# Power_Stage.net
KiCad netlist of a schematic drawn in Altium Designer
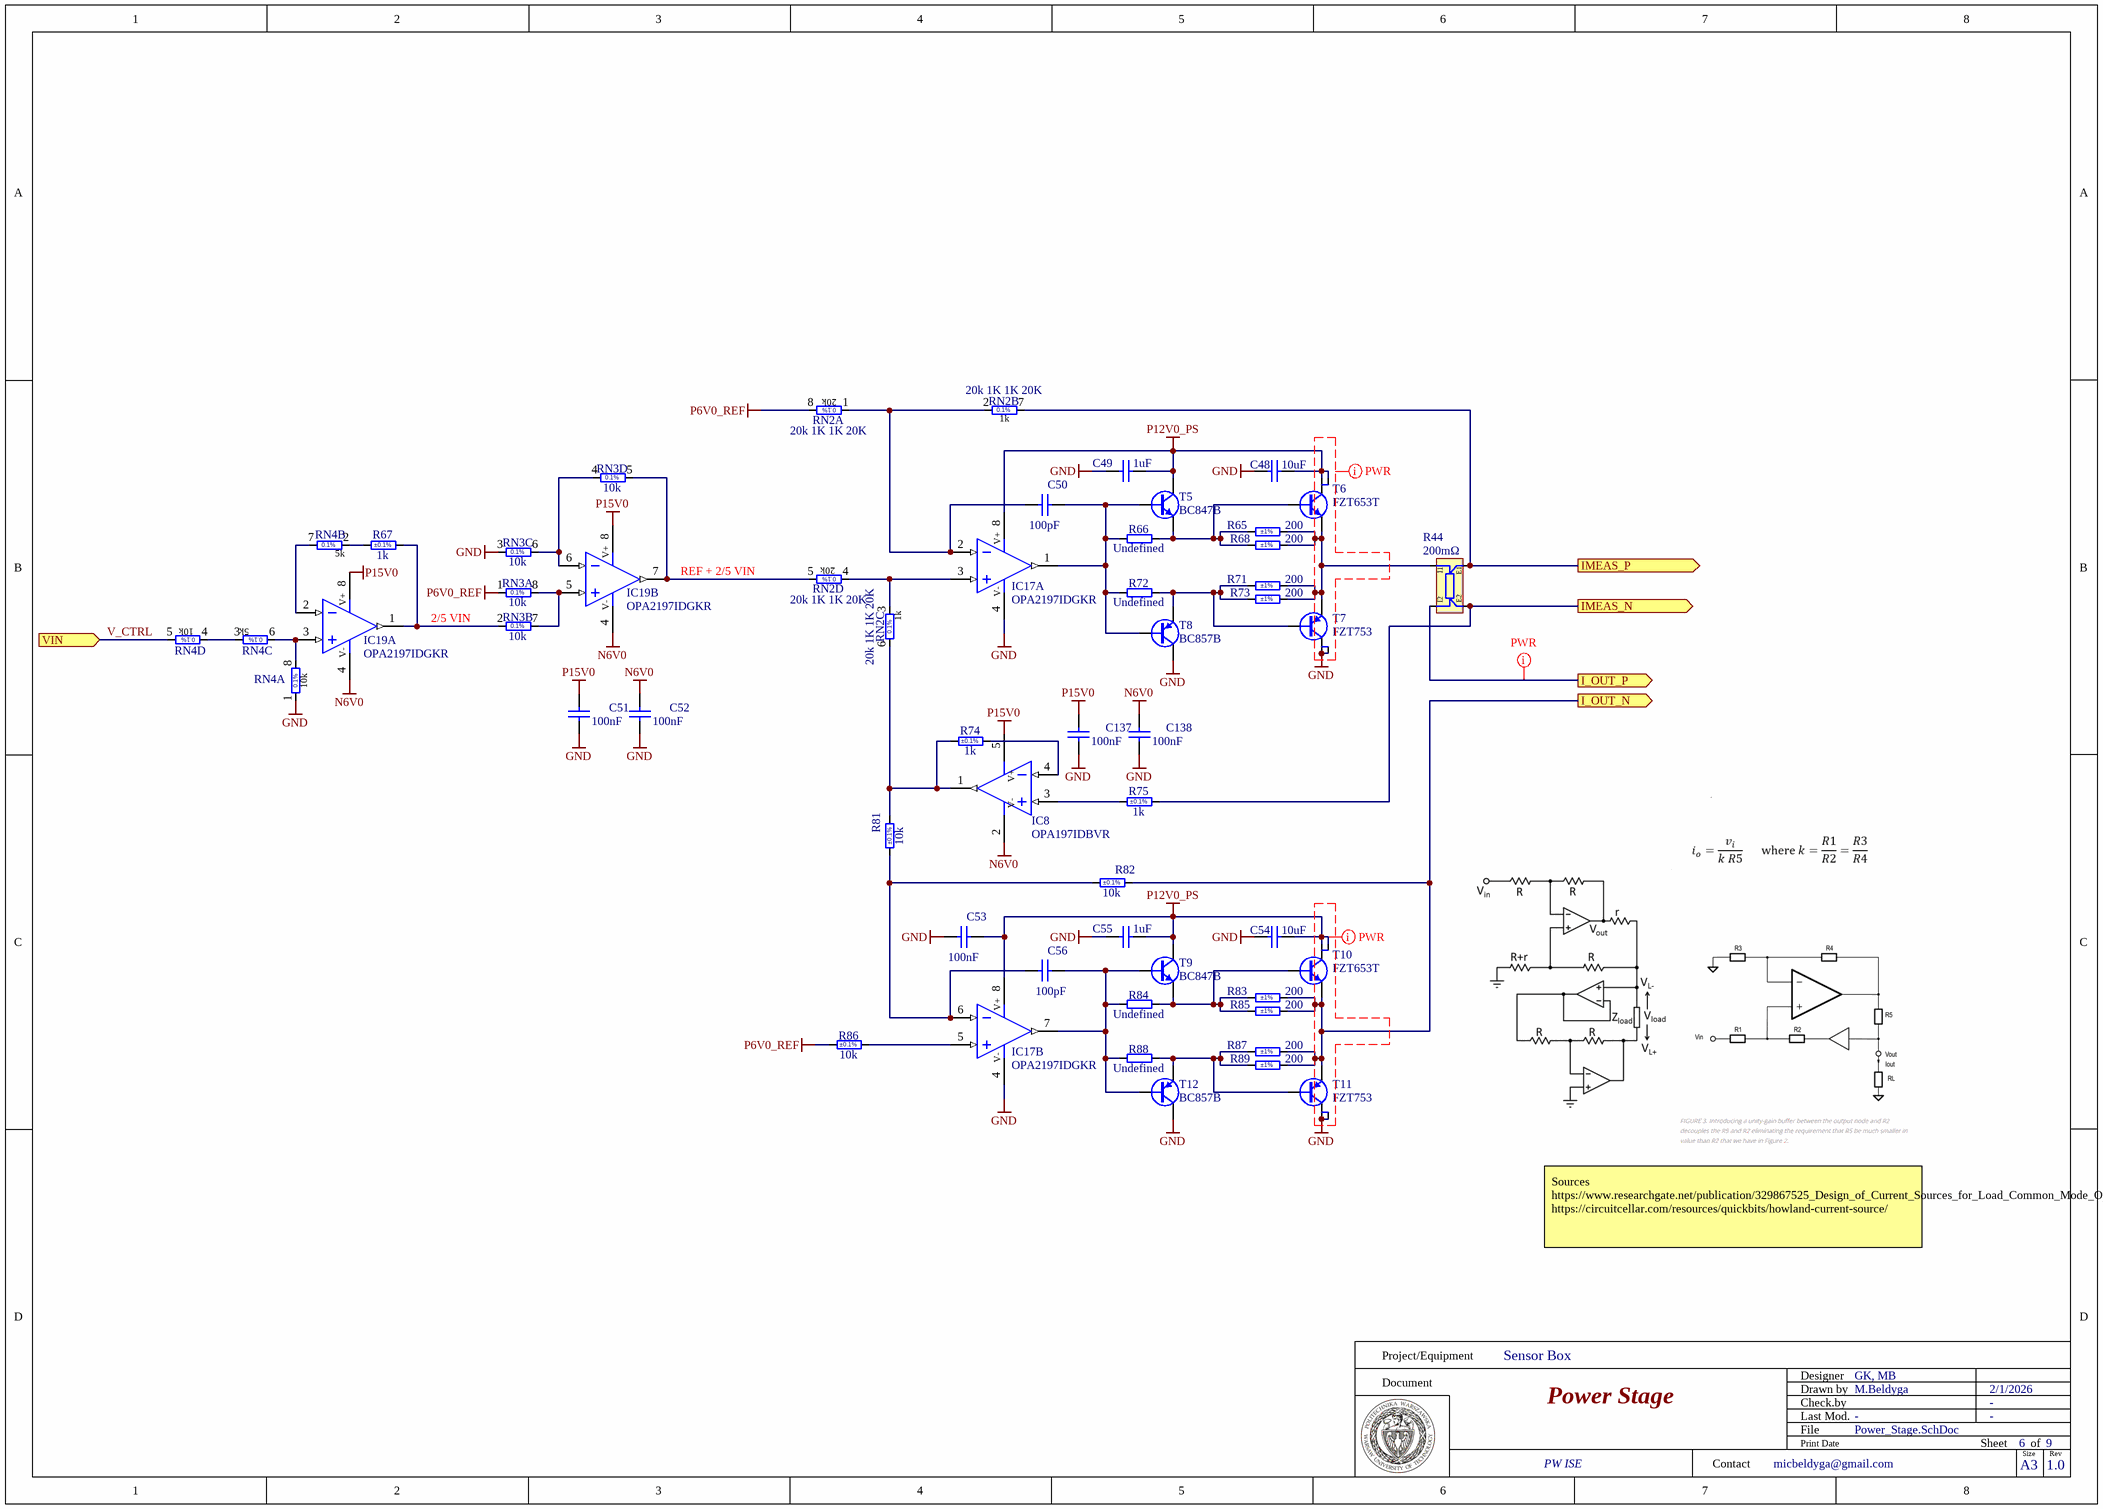
[diagram p0: Power_Stage.SchDoc]

(export (version "E")
  (design (tool "Eeschema 10.0.6"))
  (components
    (comp (ref "C48")
      (value "10uF")
      (footprint "CAPC2012X95N")
      (description "Non-polarised capacitor")
      (fields
        (field (name "PART NUMBER") "CC0805_10UF_25V_10%_X5R")
        (field (name "VOLTAGE") "25V")
        (field (name "AUTHOR") "CERN DEM JLC")
      )
      (libsource (lib "Capacitors") (part "Capacitor - non polarized"))
    )
    (comp (ref "C49")
      (value "1uF")
      (footprint "CAPC1608X87N")
      (description "Non-polarised capacitor")
      (fields
        (field (name "PART NUMBER") "CC0603_1UF_25V_10%_X7R")
        (field (name "VOLTAGE") "25V")
        (field (name "AUTHOR") "CERN DEM JLC")
      )
      (libsource (lib "Capacitors") (part "Capacitor - non polarized"))
    )
    (comp (ref "C50")
      (value "100pF")
      (footprint "CAPC1005X55N")
      (description "Non-polarised capacitor")
      (fields
        (field (name "PART NUMBER") "CC0402_100PF_50V_5%_C0G")
        (field (name "VOLTAGE") "50V")
        (field (name "AUTHOR") "CERN DEM JLC")
      )
      (libsource (lib "Capacitors") (part "Capacitor - non polarized"))
    )
    (comp (ref "C51")
      (value "100nF")
      (footprint "CAPC1005X55N")
      (description "Non-polarised capacitor")
      (fields
        (field (name "PART NUMBER") "CC0402_100NF_16V_10%_X5R")
        (field (name "VOLTAGE") "16V")
        (field (name "AUTHOR") "CERN DEM JLC")
      )
      (libsource (lib "Capacitors") (part "Capacitor - non polarized"))
    )
    (comp (ref "C52")
      (value "100nF")
      (footprint "CAPC1005X55N")
      (description "Non-polarised capacitor")
      (fields
        (field (name "PART NUMBER") "CC0402_100NF_16V_10%_X5R")
        (field (name "VOLTAGE") "16V")
        (field (name "AUTHOR") "CERN DEM JLC")
      )
      (libsource (lib "Capacitors") (part "Capacitor - non polarized"))
    )
    (comp (ref "C53")
      (value "100nF")
      (footprint "CAPC1005X55N")
      (description "Non-polarised capacitor")
      (fields
        (field (name "PART NUMBER") "CC0402_100NF_16V_10%_X5R")
        (field (name "VOLTAGE") "16V")
        (field (name "AUTHOR") "CERN DEM JLC")
      )
      (libsource (lib "Capacitors") (part "Capacitor - non polarized"))
    )
    (comp (ref "C54")
      (value "10uF")
      (footprint "CAPC2012X95N")
      (description "Non-polarised capacitor")
      (fields
        (field (name "PART NUMBER") "CC0805_10UF_25V_10%_X5R")
        (field (name "VOLTAGE") "25V")
        (field (name "AUTHOR") "CERN DEM JLC")
      )
      (libsource (lib "Capacitors") (part "Capacitor - non polarized"))
    )
    (comp (ref "C55")
      (value "1uF")
      (footprint "CAPC1608X87N")
      (description "Non-polarised capacitor")
      (fields
        (field (name "PART NUMBER") "CC0603_1UF_25V_10%_X7R")
        (field (name "VOLTAGE") "25V")
        (field (name "AUTHOR") "CERN DEM JLC")
      )
      (libsource (lib "Capacitors") (part "Capacitor - non polarized"))
    )
    (comp (ref "C56")
      (value "100pF")
      (footprint "CAPC1005X55N")
      (description "Non-polarised capacitor")
      (fields
        (field (name "PART NUMBER") "CC0402_100PF_50V_5%_C0G")
        (field (name "VOLTAGE") "50V")
        (field (name "AUTHOR") "CERN DEM JLC")
      )
      (libsource (lib "Capacitors") (part "Capacitor - non polarized"))
    )
    (comp (ref "C137")
      (value "100nF")
      (footprint "CAPC1005X55N")
      (description "Non-polarised capacitor")
      (fields
        (field (name "PART NUMBER") "CC0402_100NF_16V_10%_X5R")
        (field (name "VOLTAGE") "16V")
        (field (name "AUTHOR") "CERN DEM JLC")
      )
      (libsource (lib "Capacitors") (part "Capacitor - non polarized"))
    )
    (comp (ref "C138")
      (value "100nF")
      (footprint "CAPC1005X55N")
      (description "Non-polarised capacitor")
      (fields
        (field (name "PART NUMBER") "CC0402_100NF_16V_10%_X5R")
        (field (name "VOLTAGE") "16V")
        (field (name "AUTHOR") "CERN DEM JLC")
      )
      (libsource (lib "Capacitors") (part "Capacitor - non polarized"))
    )
    (comp (ref "IC8")
      (value "OPA197IDBVR")
      (footprint "SOT95P280X145-5N")
      (description "Op Amp Single Precision Amplifier R-R I/O ±18V/36V 5-Pin SOT-23 T/R")
      (fields (field (name "MANUFACTURER") "Texas Instruments"))
      (libsource (lib "mb") (part "OPA197IDBVR"))
    )
    (comp (ref "IC17")
      (value "OPA2197IDGKR")
      (footprint "SOP65P490X110-8N")
      (description "36-V, Precision, Rail-to-Rail Input Output, Low Offset Voltage Op Amp 8-VSSOP")
      (fields (field (name "AUTHOR") "GK"))
      (libsource (lib "ICs_Analog_Interfaces") (part "OA_OPA2197IDGKR"))
    )
    (comp (ref "IC19")
      (value "OPA2197IDGKR")
      (footprint "SOP65P490X110-8N")
      (description "36-V, Precision, Rail-to-Rail Input Output, Low Offset Voltage Op Amp 8-VSSOP")
      (fields (field (name "AUTHOR") "GK"))
      (libsource (lib "ICs_Analog_Interfaces") (part "OA_OPA2197IDGKR"))
    )
    (comp (ref "R44")
      (value "200mΩ")
      (footprint "RES_VISHAY_CSM2512_0R007-0R2")
      (description "Fixed Resistor, Metal Strip, 1W, 0.2ohm, 0.447V, 0.1% +/-Tol, 15ppm/Cel, Surface Mount, 2512")
      (fields
        (field (name "MANUFACTURER") "VPG Foil Resistors")
        (field (name "MANUFACTURER PART NUMBER") "Y14870R20000B9R")
      )
      (libsource (lib "mb") (part "Y14870R20000B9R"))
    )
    (comp (ref "R65")
      (value "200")
      (footprint "RESC1608X55N")
      (description "Resistor - 1%")
      (fields
        (field (name "TOLERANCE") "±1%")
        (field (name "PART NUMBER") "R0603_200R_1%_0.1W_100PPM")
        (field (name "POWER") "0.1W")
        (field (name "AUTHOR") "CERN DEM JLC")
      )
      (libsource (lib "Resistors") (part "Resistor - 1%"))
    )
    (comp (ref "R66")
      (value "Undefined")
      (footprint "RESC1608X55N")
      (description "Resistor")
      (fields (field (name "PART NUMBER") "R0603_NO-VALUE") (field (name "AUTHOR") "CERN DEM JLC"))
      (libsource (lib "Resistors") (part "Resistor"))
    )
    (comp (ref "R67")
      (value "1k")
      (footprint "RESC1005X40N")
      (description "Resistor - 0.1%")
      (fields
        (field (name "TOLERANCE") "±0.1%")
        (field (name "PART NUMBER") "R0402_1K_0.1%_0.063W_25PPM")
        (field (name "POWER") "0.063W")
        (field (name "AUTHOR") "CERN DEM BC")
      )
      (libsource (lib "Resistors") (part "Resistor - 0.1%"))
    )
    (comp (ref "R68")
      (value "200")
      (footprint "RESC1608X55N")
      (description "Resistor - 1%")
      (fields
        (field (name "TOLERANCE") "±1%")
        (field (name "PART NUMBER") "R0603_200R_1%_0.1W_100PPM")
        (field (name "POWER") "0.1W")
        (field (name "AUTHOR") "CERN DEM JLC")
      )
      (libsource (lib "Resistors") (part "Resistor - 1%"))
    )
    (comp (ref "R71")
      (value "200")
      (footprint "RESC1608X55N")
      (description "Resistor - 1%")
      (fields
        (field (name "TOLERANCE") "±1%")
        (field (name "PART NUMBER") "R0603_200R_1%_0.1W_100PPM")
        (field (name "POWER") "0.1W")
        (field (name "AUTHOR") "CERN DEM JLC")
      )
      (libsource (lib "Resistors") (part "Resistor - 1%"))
    )
    (comp (ref "R72")
      (value "Undefined")
      (footprint "RESC1608X55N")
      (description "Resistor")
      (fields (field (name "PART NUMBER") "R0603_NO-VALUE") (field (name "AUTHOR") "CERN DEM JLC"))
      (libsource (lib "Resistors") (part "Resistor"))
    )
    (comp (ref "R73")
      (value "200")
      (footprint "RESC1608X55N")
      (description "Resistor - 1%")
      (fields
        (field (name "TOLERANCE") "±1%")
        (field (name "PART NUMBER") "R0603_200R_1%_0.1W_100PPM")
        (field (name "POWER") "0.1W")
        (field (name "AUTHOR") "CERN DEM JLC")
      )
      (libsource (lib "Resistors") (part "Resistor - 1%"))
    )
    (comp (ref "R74")
      (value "1k")
      (footprint "RESC1005X40N")
      (description "Resistor - 0.1%")
      (fields
        (field (name "TOLERANCE") "±0.1%")
        (field (name "PART NUMBER") "R0402_1K_0.1%_0.063W_25PPM")
        (field (name "POWER") "0.063W")
        (field (name "AUTHOR") "CERN DEM BC")
      )
      (libsource (lib "Resistors") (part "Resistor - 0.1%"))
    )
    (comp (ref "R75")
      (value "1k")
      (footprint "RESC1005X40N")
      (description "Resistor - 0.1%")
      (fields
        (field (name "TOLERANCE") "±0.1%")
        (field (name "PART NUMBER") "R0402_1K_0.1%_0.063W_25PPM")
        (field (name "POWER") "0.063W")
        (field (name "AUTHOR") "CERN DEM BC")
      )
      (libsource (lib "Resistors") (part "Resistor - 0.1%"))
    )
    (comp (ref "R81")
      (value "10k")
      (footprint "RESC1005X35N")
      (description "Resistor - 0.1%")
      (fields
        (field (name "TOLERANCE") "±0.1%")
        (field (name "PART NUMBER") "R0402_10K_0.1%_0.063W_25PPM")
        (field (name "POWER") "0.063W")
        (field (name "AUTHOR") "CERN DEM JMW")
      )
      (libsource (lib "Resistors") (part "Resistor - 0.1%"))
    )
    (comp (ref "R82")
      (value "10k")
      (footprint "RESC1005X35N")
      (description "Resistor - 0.1%")
      (fields
        (field (name "TOLERANCE") "±0.1%")
        (field (name "PART NUMBER") "R0402_10K_0.1%_0.063W_25PPM")
        (field (name "POWER") "0.063W")
        (field (name "AUTHOR") "CERN DEM JMW")
      )
      (libsource (lib "Resistors") (part "Resistor - 0.1%"))
    )
    (comp (ref "R83")
      (value "200")
      (footprint "RESC1608X55N")
      (description "Resistor - 1%")
      (fields
        (field (name "TOLERANCE") "±1%")
        (field (name "PART NUMBER") "R0603_200R_1%_0.1W_100PPM")
        (field (name "POWER") "0.1W")
        (field (name "AUTHOR") "CERN DEM JLC")
      )
      (libsource (lib "Resistors") (part "Resistor - 1%"))
    )
    (comp (ref "R84")
      (value "Undefined")
      (footprint "RESC1608X55N")
      (description "Resistor")
      (fields (field (name "PART NUMBER") "R0603_NO-VALUE") (field (name "AUTHOR") "CERN DEM JLC"))
      (libsource (lib "Resistors") (part "Resistor"))
    )
    (comp (ref "R85")
      (value "200")
      (footprint "RESC1608X55N")
      (description "Resistor - 1%")
      (fields
        (field (name "TOLERANCE") "±1%")
        (field (name "PART NUMBER") "R0603_200R_1%_0.1W_100PPM")
        (field (name "POWER") "0.1W")
        (field (name "AUTHOR") "CERN DEM JLC")
      )
      (libsource (lib "Resistors") (part "Resistor - 1%"))
    )
    (comp (ref "R86")
      (value "10k")
      (footprint "RESC1005X35N")
      (description "Resistor - 0.1%")
      (fields
        (field (name "TOLERANCE") "±0.1%")
        (field (name "PART NUMBER") "R0402_10K_0.1%_0.063W_25PPM")
        (field (name "POWER") "0.063W")
        (field (name "AUTHOR") "CERN DEM JMW")
      )
      (libsource (lib "Resistors") (part "Resistor - 0.1%"))
    )
    (comp (ref "R87")
      (value "200")
      (footprint "RESC1608X55N")
      (description "Resistor - 1%")
      (fields
        (field (name "TOLERANCE") "±1%")
        (field (name "PART NUMBER") "R0603_200R_1%_0.1W_100PPM")
        (field (name "POWER") "0.1W")
        (field (name "AUTHOR") "CERN DEM JLC")
      )
      (libsource (lib "Resistors") (part "Resistor - 1%"))
    )
    (comp (ref "R88")
      (value "Undefined")
      (footprint "RESC1608X55N")
      (description "Resistor")
      (fields (field (name "PART NUMBER") "R0603_NO-VALUE") (field (name "AUTHOR") "CERN DEM JLC"))
      (libsource (lib "Resistors") (part "Resistor"))
    )
    (comp (ref "R89")
      (value "200")
      (footprint "RESC1608X55N")
      (description "Resistor - 1%")
      (fields
        (field (name "TOLERANCE") "±1%")
        (field (name "PART NUMBER") "R0603_200R_1%_0.1W_100PPM")
        (field (name "POWER") "0.1W")
        (field (name "AUTHOR") "CERN DEM JLC")
      )
      (libsource (lib "Resistors") (part "Resistor - 1%"))
    )
    (comp (ref "RN2")
      (value "20k 1K 1K 20K")
      (footprint "SOIC127P600X175-8N")
      (description "DIL8 Resistor Network 4 Resistors 4xR 10k-1k-1k-10k 0.1%")
      (fields
        (field (name "PART NUMBER") "RN_20K_1K_VISHAY_AORN10-1A")
        (field (name "POWER") "4x0.1W")
        (field (name "AUTHOR") "GK")
      )
      (libsource (lib "Passives_RC") (part "RN_20K_1K_VISHAY_AORN20-1A"))
    )
    (comp (ref "RN3")
      (value "10k")
      (footprint "SOIC127P600X175-8N")
      (description "DIL8 Resistor Network 4 Isolated Resistor 0.1%")
      (fields
        (field (name "PART NUMBER") "RN_10K_VISHAY_AORN1002A")
        (field (name "POWER") "4x0.1W")
        (field (name "AUTHOR") "CERN DEM JLC")
      )
      (libsource (lib "Resistors") (part "RN DIL8_4xR_Isolated_0.1%"))
    )
    (comp (ref "RN4")
      (value "10k 5K 5K 10K")
      (footprint "SOIC127P600X175-8N")
      (description "DIL8 Resistor Network 4 Resistors 10k-5k-5k-10k 0.1%")
      (fields
        (field (name "PART NUMBER") "RN_10K_5K_VISHAY_AORN2-1AT3")
        (field (name "POWER") "4x0.1W")
        (field (name "AUTHOR") "CERN DEM JLC")
      )
      (libsource (lib "Resistors") (part "RN DIL8_4xR_10k-5k-5k-10k_0.1%"))
    )
    (comp (ref "T5")
      (value "BC847B")
      (footprint "SOT95P230X110-3N")
      (description "NPN Transistor")
      (fields (field (name "MANUFACTURER") "NXP SEMICONDUCTORS") (field (name "AUTHOR") "CERN DEM JLC"))
      (libsource (lib "ICs And Semiconductors") (part "NPN B1 E2 C3"))
    )
    (comp (ref "T6")
      (value "FZT653T")
      (footprint "SOT230P700X180-4N")
      (description "NPN Transistor")
      (fields (field (name "MANUFACTURER") "ZETEX SEMICONDUCTORS") (field (name "AUTHOR") "CERN DEM HF"))
      (libsource (lib "ICs And Semiconductors") (part "NPN B1 C2 E3 C4"))
    )
    (comp (ref "T7")
      (value "FZT753")
      (footprint "SOT230P700X180-4N")
      (description "PNP Transistor")
      (fields (field (name "MANUFACTURER") "DIODES INCORPORATED") (field (name "AUTHOR") "CERN DEM JLC"))
      (libsource (lib "ICs And Semiconductors") (part "PNP B1 C2 E3 C4"))
    )
    (comp (ref "T8")
      (value "BC857B")
      (footprint "SOT95P230X110-3N")
      (description "PNP Transistor")
      (fields (field (name "MANUFACTURER") "NXP SEMICONDUCTORS") (field (name "AUTHOR") "CERN DEM JLC"))
      (libsource (lib "ICs And Semiconductors") (part "PNP B1 E2 C3"))
    )
    (comp (ref "T9")
      (value "BC847B")
      (footprint "SOT95P230X110-3N")
      (description "NPN Transistor")
      (fields (field (name "MANUFACTURER") "NXP SEMICONDUCTORS") (field (name "AUTHOR") "CERN DEM JLC"))
      (libsource (lib "ICs And Semiconductors") (part "NPN B1 E2 C3"))
    )
    (comp (ref "T10")
      (value "FZT653T")
      (footprint "SOT230P700X180-4N")
      (description "NPN Transistor")
      (fields (field (name "MANUFACTURER") "ZETEX SEMICONDUCTORS") (field (name "AUTHOR") "CERN DEM HF"))
      (libsource (lib "ICs And Semiconductors") (part "NPN B1 C2 E3 C4"))
    )
    (comp (ref "T11")
      (value "FZT753")
      (footprint "SOT230P700X180-4N")
      (description "PNP Transistor")
      (fields (field (name "MANUFACTURER") "DIODES INCORPORATED") (field (name "AUTHOR") "CERN DEM JLC"))
      (libsource (lib "ICs And Semiconductors") (part "PNP B1 C2 E3 C4"))
    )
    (comp (ref "T12")
      (value "BC857B")
      (footprint "SOT95P230X110-3N")
      (description "PNP Transistor")
      (fields (field (name "MANUFACTURER") "NXP SEMICONDUCTORS") (field (name "AUTHOR") "CERN DEM JLC"))
      (libsource (lib "ICs And Semiconductors") (part "PNP B1 E2 C3"))
    )
  )
  (nets
    (net (code "1") (name "/IMEAS_N") (class "Default")
      (node (ref "R44") (pin "E2") (pinfunction "E2_E2") (pintype "passive"))
      (node (ref "R75") (pin "2") (pinfunction "2_2") (pintype "passive"))
    )
    (net (code "2") (name "/IMEAS_P") (class "Default")
      (node (ref "R44") (pin "E1") (pinfunction "E1_E1") (pintype "passive"))
      (node (ref "RN2") (pin "7") (pinfunction "7_7") (pintype "passive"))
    )
    (net (code "3") (name "/I_OUT_N") (class "Default")
      (node (ref "R82") (pin "2") (pinfunction "2_2") (pintype "passive"))
      (node (ref "R83") (pin "2") (pinfunction "2_2") (pintype "passive"))
      (node (ref "R85") (pin "2") (pinfunction "2_2") (pintype "passive"))
      (node (ref "R87") (pin "2") (pinfunction "2_2") (pintype "passive"))
      (node (ref "R89") (pin "2") (pinfunction "2_2") (pintype "passive"))
      (node (ref "T10") (pin "3") (pinfunction "E_3") (pintype "passive"))
      (node (ref "T11") (pin "3") (pinfunction "E_3") (pintype "passive"))
    )
    (net (code "4") (name "/I_OUT_P") (class "Default")
      (node (ref "R44") (pin "I2") (pinfunction "I2_I2") (pintype "passive"))
    )
    (net (code "5") (name "/V_CTRL") (class "Default")
      (node (ref "RN4") (pin "5") (pinfunction "5_5") (pintype "passive"))
    )
    (net (code "6") (name "GND") (class "Default")
      (node (ref "C137") (pin "1") (pinfunction "1_1") (pintype "passive"))
      (node (ref "C138") (pin "1") (pinfunction "1_1") (pintype "passive"))
      (node (ref "C48") (pin "2") (pinfunction "2_2") (pintype "passive"))
      (node (ref "C49") (pin "1") (pinfunction "1_1") (pintype "passive"))
      (node (ref "C51") (pin "1") (pinfunction "1_1") (pintype "passive"))
      (node (ref "C52") (pin "1") (pinfunction "1_1") (pintype "passive"))
      (node (ref "C53") (pin "1") (pinfunction "1_1") (pintype "passive"))
      (node (ref "C54") (pin "2") (pinfunction "2_2") (pintype "passive"))
      (node (ref "C55") (pin "1") (pinfunction "1_1") (pintype "passive"))
      (node (ref "IC17") (pin "4") (pinfunction "V-_4") (pintype "power_in"))
      (node (ref "RN3") (pin "3") (pinfunction "3_3") (pintype "passive"))
      (node (ref "RN4") (pin "1") (pinfunction "1_1") (pintype "passive"))
      (node (ref "T11") (pin "2") (pinfunction "C_2") (pintype "passive"))
      (node (ref "T11") (pin "4") (pinfunction "C_4") (pintype "passive"))
      (node (ref "T12") (pin "3") (pinfunction "C_3") (pintype "passive"))
      (node (ref "T7") (pin "2") (pinfunction "C_2") (pintype "passive"))
      (node (ref "T7") (pin "4") (pinfunction "C_4") (pintype "passive"))
      (node (ref "T8") (pin "3") (pinfunction "C_3") (pintype "passive"))
    )
    (net (code "7") (name "N6V0") (class "Default")
      (node (ref "C138") (pin "2") (pinfunction "2_2") (pintype "passive"))
      (node (ref "C52") (pin "2") (pinfunction "2_2") (pintype "passive"))
      (node (ref "IC19") (pin "4") (pinfunction "V-_4") (pintype "power_in"))
      (node (ref "IC8") (pin "2") (pinfunction "V-_2") (pintype "power_in"))
    )
    (net (code "8") (name "Net-(IC8-IN+)") (class "Default")
      (node (ref "IC8") (pin "3") (pinfunction "IN+_3") (pintype "input"))
      (node (ref "R75") (pin "1") (pinfunction "1_1") (pintype "passive"))
    )
    (net (code "9") (name "Net-(IC8-IN-)") (class "Default")
      (node (ref "IC8") (pin "4") (pinfunction "IN-_4") (pintype "input"))
      (node (ref "R74") (pin "2") (pinfunction "2_2") (pintype "passive"))
    )
    (net (code "10") (name "Net-(IC8-OUT)") (class "Default")
      (node (ref "IC8") (pin "1") (pinfunction "OUT_1") (pintype "output"))
      (node (ref "R74") (pin "1") (pinfunction "1_1") (pintype "passive"))
      (node (ref "R81") (pin "2") (pinfunction "2_2") (pintype "passive"))
      (node (ref "RN2") (pin "6") (pinfunction "6_6") (pintype "passive"))
    )
    (net (code "11") (name "Net-(IC17A-IN+)") (class "Default")
      (node (ref "IC17") (pin "3") (pinfunction "IN+_3") (pintype "input"))
      (node (ref "RN2") (pin "3") (pinfunction "3_3") (pintype "passive"))
      (node (ref "RN2") (pin "4") (pinfunction "4_4") (pintype "passive"))
    )
    (net (code "12") (name "Net-(IC17A-IN-)") (class "Default")
      (node (ref "C50") (pin "1") (pinfunction "1_1") (pintype "passive"))
      (node (ref "IC17") (pin "2") (pinfunction "IN-_2") (pintype "input"))
      (node (ref "RN2") (pin "1") (pinfunction "1_1") (pintype "passive"))
      (node (ref "RN2") (pin "2") (pinfunction "2_2") (pintype "passive"))
    )
    (net (code "13") (name "Net-(IC17A-OUT)") (class "Default")
      (node (ref "C50") (pin "2") (pinfunction "2_2") (pintype "passive"))
      (node (ref "IC17") (pin "1") (pinfunction "OUT_1") (pintype "output"))
      (node (ref "R66") (pin "1") (pinfunction "1_1") (pintype "passive"))
      (node (ref "R72") (pin "1") (pinfunction "1_1") (pintype "passive"))
      (node (ref "T5") (pin "1") (pinfunction "B_1") (pintype "passive"))
      (node (ref "T8") (pin "1") (pinfunction "B_1") (pintype "passive"))
    )
    (net (code "14") (name "Net-(IC17B-IN+)") (class "Default")
      (node (ref "IC17") (pin "5") (pinfunction "IN+_5") (pintype "input"))
      (node (ref "R86") (pin "2") (pinfunction "2_2") (pintype "passive"))
    )
    (net (code "15") (name "Net-(IC17B-IN-)") (class "Default")
      (node (ref "C56") (pin "1") (pinfunction "1_1") (pintype "passive"))
      (node (ref "IC17") (pin "6") (pinfunction "IN-_6") (pintype "input"))
      (node (ref "R81") (pin "1") (pinfunction "1_1") (pintype "passive"))
      (node (ref "R82") (pin "1") (pinfunction "1_1") (pintype "passive"))
    )
    (net (code "16") (name "Net-(IC17B-OUT)") (class "Default")
      (node (ref "C56") (pin "2") (pinfunction "2_2") (pintype "passive"))
      (node (ref "IC17") (pin "7") (pinfunction "OUT_7") (pintype "output"))
      (node (ref "R84") (pin "1") (pinfunction "1_1") (pintype "passive"))
      (node (ref "R88") (pin "1") (pinfunction "1_1") (pintype "passive"))
      (node (ref "T12") (pin "1") (pinfunction "B_1") (pintype "passive"))
      (node (ref "T9") (pin "1") (pinfunction "B_1") (pintype "passive"))
    )
    (net (code "17") (name "Net-(IC19A-IN+)") (class "Default")
      (node (ref "IC19") (pin "3") (pinfunction "IN+_3") (pintype "input"))
      (node (ref "RN4") (pin "6") (pinfunction "6_6") (pintype "passive"))
      (node (ref "RN4") (pin "8") (pinfunction "8_8") (pintype "passive"))
    )
    (net (code "18") (name "Net-(IC19A-IN-)") (class "Default")
      (node (ref "IC19") (pin "2") (pinfunction "IN-_2") (pintype "input"))
      (node (ref "RN4") (pin "7") (pinfunction "7_7") (pintype "passive"))
    )
    (net (code "19") (name "Net-(IC19A-OUT)") (class "Default")
      (node (ref "IC19") (pin "1") (pinfunction "OUT_1") (pintype "output"))
      (node (ref "R67") (pin "2") (pinfunction "2_2") (pintype "passive"))
      (node (ref "RN3") (pin "2") (pinfunction "2_2") (pintype "passive"))
    )
    (net (code "20") (name "Net-(IC19B-IN+)") (class "Default")
      (node (ref "IC19") (pin "5") (pinfunction "IN+_5") (pintype "input"))
      (node (ref "RN3") (pin "7") (pinfunction "7_7") (pintype "passive"))
      (node (ref "RN3") (pin "8") (pinfunction "8_8") (pintype "passive"))
    )
    (net (code "21") (name "Net-(IC19B-IN-)") (class "Default")
      (node (ref "IC19") (pin "6") (pinfunction "IN-_6") (pintype "input"))
      (node (ref "RN3") (pin "4") (pinfunction "4_4") (pintype "passive"))
      (node (ref "RN3") (pin "6") (pinfunction "6_6") (pintype "passive"))
    )
    (net (code "22") (name "Net-(IC19B-OUT)") (class "Default")
      (node (ref "IC19") (pin "7") (pinfunction "OUT_7") (pintype "output"))
      (node (ref "RN2") (pin "5") (pinfunction "5_5") (pintype "passive"))
      (node (ref "RN3") (pin "5") (pinfunction "5_5") (pintype "passive"))
    )
    (net (code "23") (name "Net-(R67-Pad1)") (class "Default")
      (node (ref "R67") (pin "1") (pinfunction "1_1") (pintype "passive"))
      (node (ref "RN4") (pin "2") (pinfunction "2_2") (pintype "passive"))
    )
    (net (code "24") (name "Net-(RN4-Pad3)") (class "Default")
      (node (ref "RN4") (pin "3") (pinfunction "3_3") (pintype "passive"))
      (node (ref "RN4") (pin "4") (pinfunction "4_4") (pintype "passive"))
    )
    (net (code "25") (name "Net-(T5-E)") (class "Default")
      (node (ref "R65") (pin "1") (pinfunction "1_1") (pintype "passive"))
      (node (ref "R66") (pin "2") (pinfunction "2_2") (pintype "passive"))
      (node (ref "R68") (pin "1") (pinfunction "1_1") (pintype "passive"))
      (node (ref "T5") (pin "2") (pinfunction "E_2") (pintype "passive"))
      (node (ref "T6") (pin "1") (pinfunction "B_1") (pintype "passive"))
    )
    (net (code "26") (name "Net-(T6-E)") (class "Default")
      (node (ref "R44") (pin "I1") (pinfunction "I1_I1") (pintype "passive"))
      (node (ref "R65") (pin "2") (pinfunction "2_2") (pintype "passive"))
      (node (ref "R68") (pin "2") (pinfunction "2_2") (pintype "passive"))
      (node (ref "R71") (pin "2") (pinfunction "2_2") (pintype "passive"))
      (node (ref "R73") (pin "2") (pinfunction "2_2") (pintype "passive"))
      (node (ref "T6") (pin "3") (pinfunction "E_3") (pintype "passive"))
      (node (ref "T7") (pin "3") (pinfunction "E_3") (pintype "passive"))
    )
    (net (code "27") (name "Net-(T7-B)") (class "Default")
      (node (ref "R71") (pin "1") (pinfunction "1_1") (pintype "passive"))
      (node (ref "R72") (pin "2") (pinfunction "2_2") (pintype "passive"))
      (node (ref "R73") (pin "1") (pinfunction "1_1") (pintype "passive"))
      (node (ref "T7") (pin "1") (pinfunction "B_1") (pintype "passive"))
      (node (ref "T8") (pin "2") (pinfunction "E_2") (pintype "passive"))
    )
    (net (code "28") (name "Net-(T10-B)") (class "Default")
      (node (ref "R83") (pin "1") (pinfunction "1_1") (pintype "passive"))
      (node (ref "R84") (pin "2") (pinfunction "2_2") (pintype "passive"))
      (node (ref "R85") (pin "1") (pinfunction "1_1") (pintype "passive"))
      (node (ref "T10") (pin "1") (pinfunction "B_1") (pintype "passive"))
      (node (ref "T9") (pin "2") (pinfunction "E_2") (pintype "passive"))
    )
    (net (code "29") (name "Net-(T11-B)") (class "Default")
      (node (ref "R87") (pin "1") (pinfunction "1_1") (pintype "passive"))
      (node (ref "R88") (pin "2") (pinfunction "2_2") (pintype "passive"))
      (node (ref "R89") (pin "1") (pinfunction "1_1") (pintype "passive"))
      (node (ref "T11") (pin "1") (pinfunction "B_1") (pintype "passive"))
      (node (ref "T12") (pin "2") (pinfunction "E_2") (pintype "passive"))
    )
    (net (code "30") (name "P6V0_REF") (class "Default")
      (node (ref "R86") (pin "1") (pinfunction "1_1") (pintype "passive"))
      (node (ref "RN2") (pin "8") (pinfunction "8_8") (pintype "passive"))
      (node (ref "RN3") (pin "1") (pinfunction "1_1") (pintype "passive"))
    )
    (net (code "31") (name "P12V0_PS") (class "Default")
      (node (ref "C48") (pin "1") (pinfunction "1_1") (pintype "passive"))
      (node (ref "C49") (pin "2") (pinfunction "2_2") (pintype "passive"))
      (node (ref "C53") (pin "2") (pinfunction "2_2") (pintype "passive"))
      (node (ref "C54") (pin "1") (pinfunction "1_1") (pintype "passive"))
      (node (ref "C55") (pin "2") (pinfunction "2_2") (pintype "passive"))
      (node (ref "IC17") (pin "8") (pinfunction "V+_8") (pintype "power_in"))
      (node (ref "T10") (pin "2") (pinfunction "C_2") (pintype "passive"))
      (node (ref "T10") (pin "4") (pinfunction "C_4") (pintype "passive"))
      (node (ref "T5") (pin "3") (pinfunction "C_3") (pintype "passive"))
      (node (ref "T6") (pin "2") (pinfunction "C_2") (pintype "passive"))
      (node (ref "T6") (pin "4") (pinfunction "C_4") (pintype "passive"))
      (node (ref "T9") (pin "3") (pinfunction "C_3") (pintype "passive"))
    )
    (net (code "32") (name "P15V0") (class "Default")
      (node (ref "C137") (pin "2") (pinfunction "2_2") (pintype "passive"))
      (node (ref "C51") (pin "2") (pinfunction "2_2") (pintype "passive"))
      (node (ref "IC19") (pin "8") (pinfunction "V+_8") (pintype "power_in"))
      (node (ref "IC8") (pin "5") (pinfunction "V+_5") (pintype "power_in"))
    )
  )
)
